# 03_POWER.net
KiCad netlist of a schematic drawn in Altium Designer
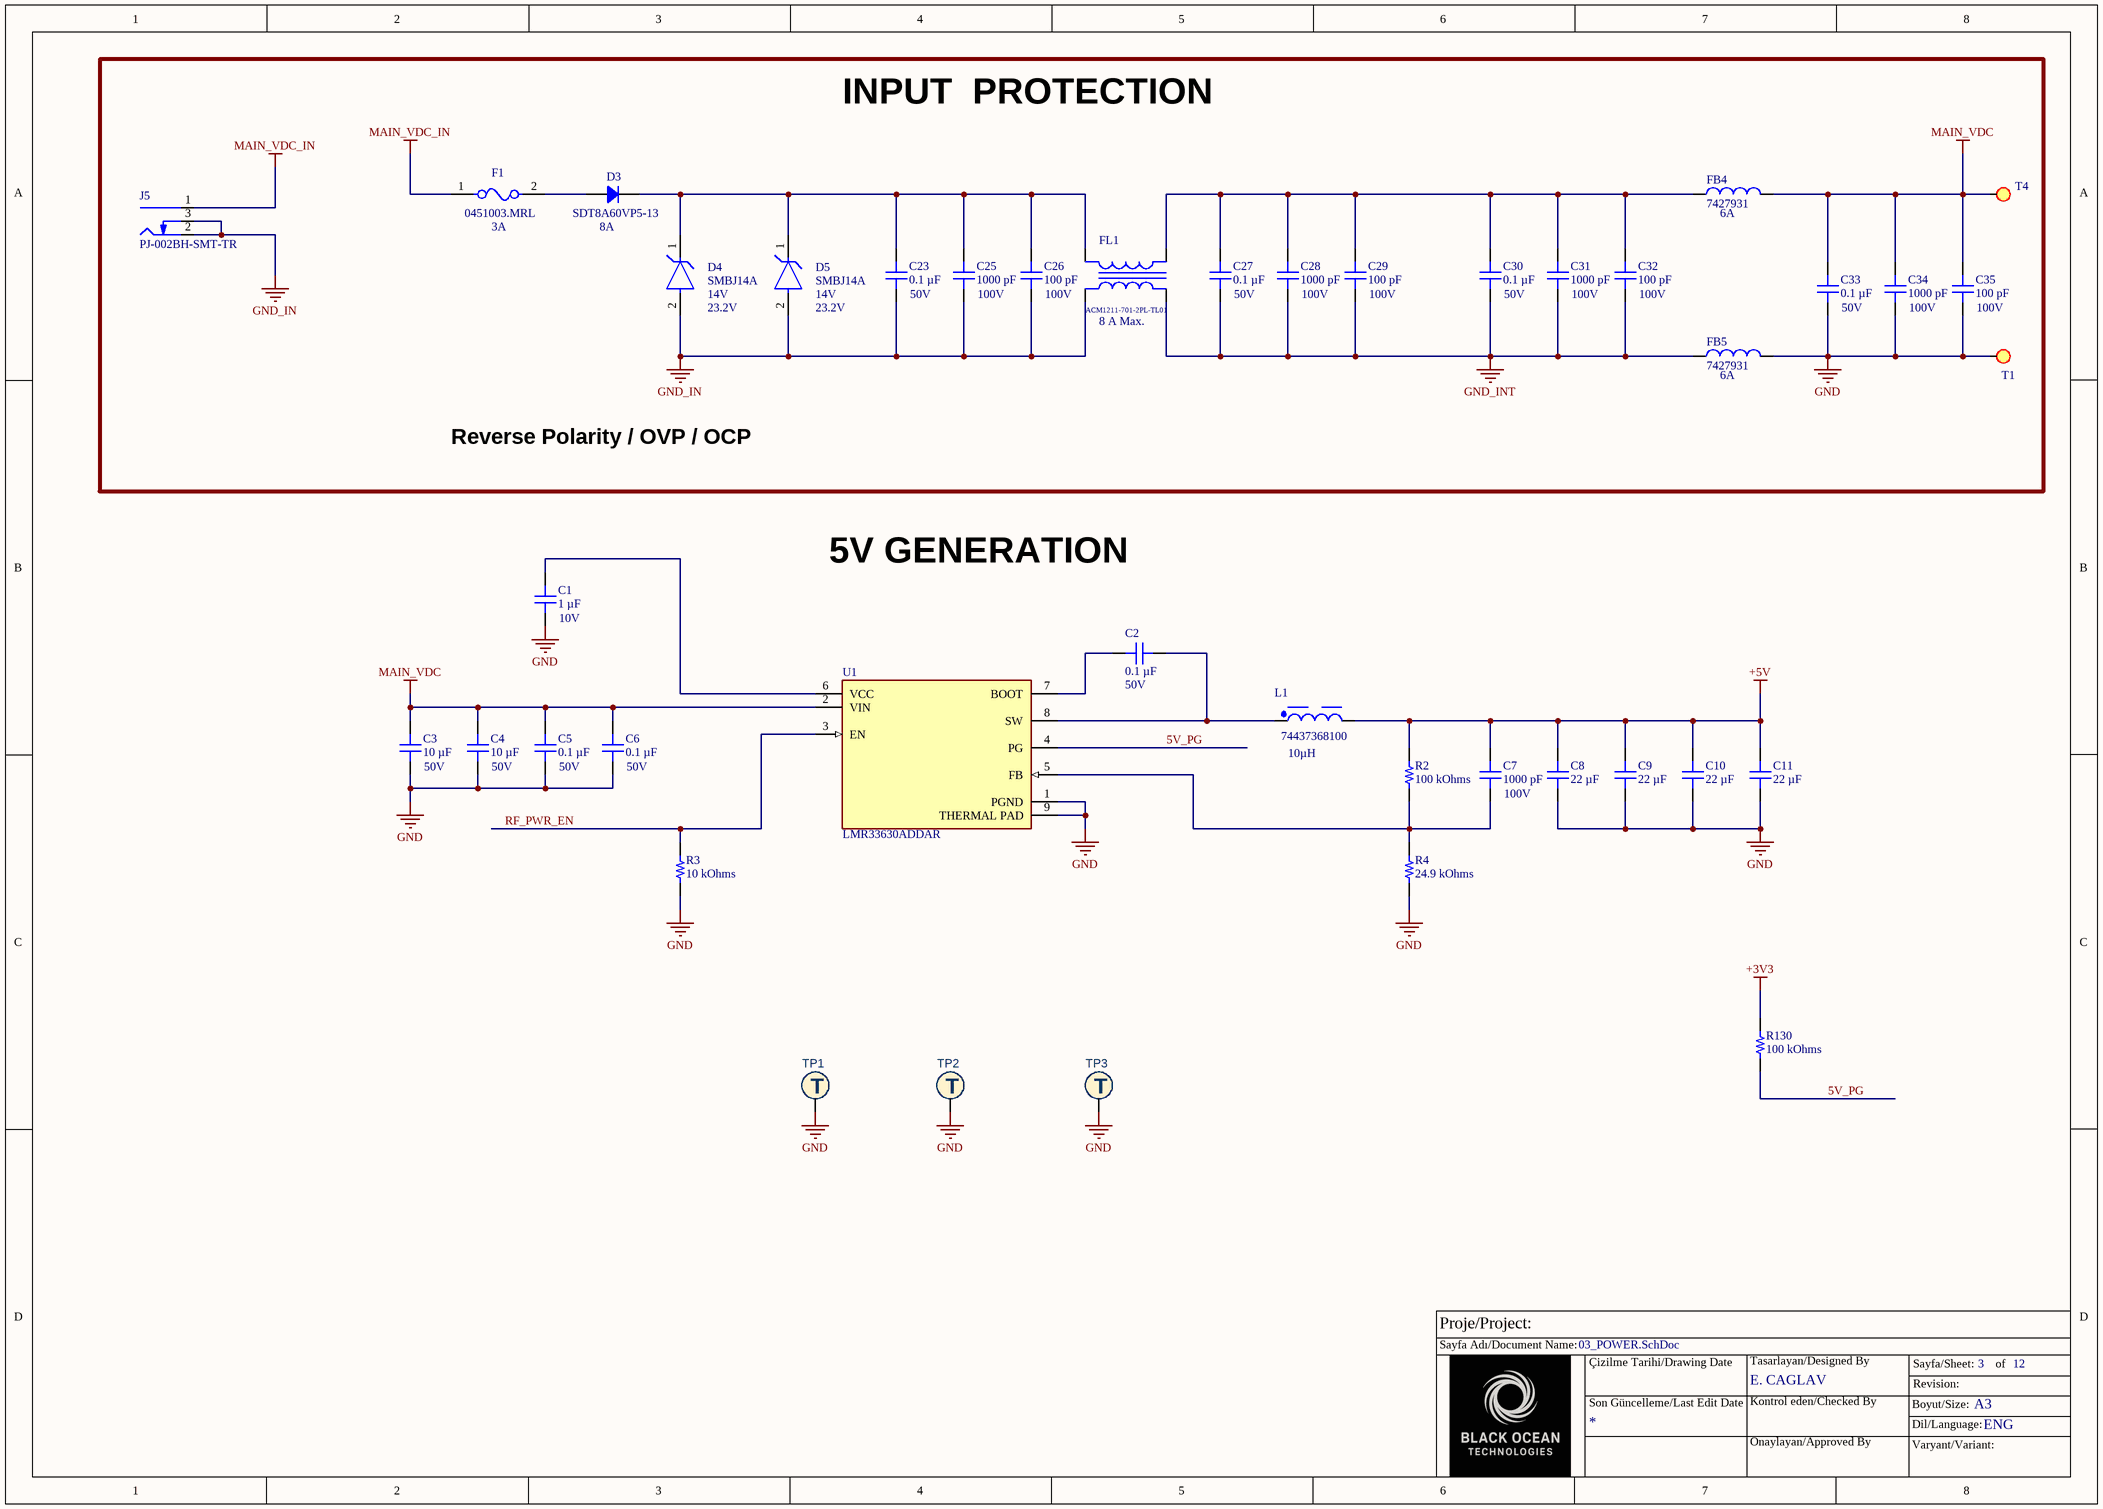
[diagram p0: 03_POWER.SchDoc]

(export (version "E")
  (design (tool "Eeschema 10.0.6"))
  (components
    (comp (ref "C1")
      (value "1 µF")
      (footprint "MURATA GRM155 0402_1005")
      (description "CAP CER 1UF 10V X7S 0402")
      (fields
        (field (name "PART NUMBER") "GRM155C71A105KE11D")
        (field (name "CAPACITANCE") "1 µF")
        (field (name "MANUFACTURER") "Murata Electronics")
        (field (name "VOLTAGE - RATED") "10V")
      )
      (libsource (lib "Celestial Altium Library - altium_library") (part "Capacitor"))
    )
    (comp (ref "C2")
      (value "0.1 µF")
      (footprint "CAP 0402_1005")
      (description "CAP CER 0.1UF 50V X7R 0402")
      (fields
        (field (name "PART NUMBER") "GCM155R71H104KE02J")
        (field (name "CAPACITANCE") "0.1 µF")
        (field (name "MANUFACTURER") "Murata Electronics")
        (field (name "VOLTAGE - RATED") "50V")
      )
      (libsource (lib "Celestial Altium Library - altium_library") (part "Capacitor"))
    )
    (comp (ref "C3")
      (value "10 µF")
      (footprint "CAP 1206_3216 - 0.8MM")
      (description "CAP CER 10UF 50V X7R 1206")
      (fields
        (field (name "PART NUMBER") "CL31B106KBHNNNE")
        (field (name "CAPACITANCE") "10 µF")
        (field (name "MANUFACTURER") "Samsung Electro-Mechanics")
        (field (name "VOLTAGE - RATED") "50V")
      )
      (libsource (lib "Celestial Altium Library - altium_library") (part "Capacitor"))
    )
    (comp (ref "C4")
      (value "10 µF")
      (footprint "CAP 1206_3216 - 0.8MM")
      (description "CAP CER 10UF 50V X7R 1206")
      (fields
        (field (name "PART NUMBER") "CL31B106KBHNNNE")
        (field (name "CAPACITANCE") "10 µF")
        (field (name "MANUFACTURER") "Samsung Electro-Mechanics")
        (field (name "VOLTAGE - RATED") "50V")
      )
      (libsource (lib "Celestial Altium Library - altium_library") (part "Capacitor"))
    )
    (comp (ref "C5")
      (value "0.1 µF")
      (footprint "CAP 0402_1005")
      (description "CAP CER 0.1UF 50V X7R 0402")
      (fields
        (field (name "PART NUMBER") "GCM155R71H104KE02J")
        (field (name "CAPACITANCE") "0.1 µF")
        (field (name "MANUFACTURER") "Murata Electronics")
        (field (name "VOLTAGE - RATED") "50V")
      )
      (libsource (lib "Celestial Altium Library - altium_library") (part "Capacitor"))
    )
    (comp (ref "C6")
      (value "0.1 µF")
      (footprint "CAP 0402_1005")
      (description "CAP CER 0.1UF 50V X7R 0402")
      (fields
        (field (name "PART NUMBER") "GCM155R71H104KE02J")
        (field (name "CAPACITANCE") "0.1 µF")
        (field (name "MANUFACTURER") "Murata Electronics")
        (field (name "VOLTAGE - RATED") "50V")
      )
      (libsource (lib "Celestial Altium Library - altium_library") (part "Capacitor"))
    )
    (comp (ref "C7")
      (value "1000 pF")
      (footprint "CAP 0402_1005")
      (description "CAP CER 1000PF 100V C0G/NP0 0402")
      (fields
        (field (name "PART NUMBER") "C0402H102J1GAC7867")
        (field (name "CAPACITANCE") "1000 pF")
        (field (name "MANUFACTURER") "KEMET")
        (field (name "VOLTAGE - RATED") "100V")
      )
      (libsource (lib "Celestial Altium Library - altium_library") (part "Capacitor"))
    )
    (comp (ref "C8")
      (value "22 µF")
      (footprint "CAP 0805_2012")
      (description "CAP CER 22UF 16V X5R 0805")
      (fields
        (field (name "PART NUMBER") "CL21A226KOQNNNE")
        (field (name "CAPACITANCE") "22 µF")
        (field (name "MANUFACTURER") "Samsung Electro-Mechanics")
      )
      (libsource (lib "Celestial Altium Library - altium_library") (part "Capacitor"))
    )
    (comp (ref "C9")
      (value "22 µF")
      (footprint "CAP 0805_2012")
      (description "CAP CER 22UF 16V X5R 0805")
      (fields
        (field (name "PART NUMBER") "CL21A226KOQNNNE")
        (field (name "CAPACITANCE") "22 µF")
        (field (name "MANUFACTURER") "Samsung Electro-Mechanics")
      )
      (libsource (lib "Celestial Altium Library - altium_library") (part "Capacitor"))
    )
    (comp (ref "C10")
      (value "22 µF")
      (footprint "CAP 0805_2012")
      (description "CAP CER 22UF 16V X5R 0805")
      (fields
        (field (name "PART NUMBER") "CL21A226KOQNNNE")
        (field (name "CAPACITANCE") "22 µF")
        (field (name "MANUFACTURER") "Samsung Electro-Mechanics")
      )
      (libsource (lib "Celestial Altium Library - altium_library") (part "Capacitor"))
    )
    (comp (ref "C11")
      (value "22 µF")
      (footprint "CAP 0805_2012")
      (description "CAP CER 22UF 16V X5R 0805")
      (fields
        (field (name "PART NUMBER") "CL21A226KOQNNNE")
        (field (name "CAPACITANCE") "22 µF")
        (field (name "MANUFACTURER") "Samsung Electro-Mechanics")
      )
      (libsource (lib "Celestial Altium Library - altium_library") (part "Capacitor"))
    )
    (comp (ref "C23")
      (value "0.1 µF")
      (footprint "CAP 0402_1005")
      (description "CAP CER 0.1UF 50V X7R 0402")
      (fields
        (field (name "PART NUMBER") "GCM155R71H104KE02J")
        (field (name "CAPACITANCE") "0.1 µF")
        (field (name "MANUFACTURER") "Murata Electronics")
        (field (name "VOLTAGE - RATED") "50V")
      )
      (libsource (lib "Celestial Altium Library - altium_library") (part "Capacitor"))
    )
    (comp (ref "C25")
      (value "1000 pF")
      (footprint "CAP 0402_1005")
      (description "CAP CER 1000PF 100V C0G/NP0 0402")
      (fields
        (field (name "PART NUMBER") "C0402H102J1GAC7867")
        (field (name "CAPACITANCE") "1000 pF")
        (field (name "MANUFACTURER") "KEMET")
        (field (name "VOLTAGE - RATED") "100V")
      )
      (libsource (lib "Celestial Altium Library - altium_library") (part "Capacitor"))
    )
    (comp (ref "C26")
      (value "100 pF")
      (footprint "CAP 0402_1005")
      (description "CAP CER 100PF 100V C0G/NPO 0402")
      (fields
        (field (name "PART NUMBER") "CC0402JRNPO0BN101")
        (field (name "CAPACITANCE") "100 pF")
        (field (name "MANUFACTURER") "Yageo")
        (field (name "VOLTAGE - RATED") "100V")
      )
      (libsource (lib "Celestial Altium Library - altium_library") (part "Capacitor"))
    )
    (comp (ref "C27")
      (value "0.1 µF")
      (footprint "CAP 0402_1005")
      (description "CAP CER 0.1UF 50V X7R 0402")
      (fields
        (field (name "PART NUMBER") "GCM155R71H104KE02J")
        (field (name "CAPACITANCE") "0.1 µF")
        (field (name "MANUFACTURER") "Murata Electronics")
        (field (name "VOLTAGE - RATED") "50V")
      )
      (libsource (lib "Celestial Altium Library - altium_library") (part "Capacitor"))
    )
    (comp (ref "C28")
      (value "1000 pF")
      (footprint "CAP 0402_1005")
      (description "CAP CER 1000PF 100V C0G/NP0 0402")
      (fields
        (field (name "PART NUMBER") "C0402H102J1GAC7867")
        (field (name "CAPACITANCE") "1000 pF")
        (field (name "MANUFACTURER") "KEMET")
        (field (name "VOLTAGE - RATED") "100V")
      )
      (libsource (lib "Celestial Altium Library - altium_library") (part "Capacitor"))
    )
    (comp (ref "C29")
      (value "100 pF")
      (footprint "CAP 0402_1005")
      (description "CAP CER 100PF 100V C0G/NPO 0402")
      (fields
        (field (name "PART NUMBER") "CC0402JRNPO0BN101")
        (field (name "CAPACITANCE") "100 pF")
        (field (name "MANUFACTURER") "Yageo")
        (field (name "VOLTAGE - RATED") "100V")
      )
      (libsource (lib "Celestial Altium Library - altium_library") (part "Capacitor"))
    )
    (comp (ref "C30")
      (value "0.1 µF")
      (footprint "CAP 0402_1005")
      (description "CAP CER 0.1UF 50V X7R 0402")
      (fields
        (field (name "PART NUMBER") "GCM155R71H104KE02J")
        (field (name "CAPACITANCE") "0.1 µF")
        (field (name "MANUFACTURER") "Murata Electronics")
        (field (name "VOLTAGE - RATED") "50V")
      )
      (libsource (lib "Celestial Altium Library - altium_library") (part "Capacitor"))
    )
    (comp (ref "C31")
      (value "1000 pF")
      (footprint "CAP 0402_1005")
      (description "CAP CER 1000PF 100V C0G/NP0 0402")
      (fields
        (field (name "PART NUMBER") "C0402H102J1GAC7867")
        (field (name "CAPACITANCE") "1000 pF")
        (field (name "MANUFACTURER") "KEMET")
        (field (name "VOLTAGE - RATED") "100V")
      )
      (libsource (lib "Celestial Altium Library - altium_library") (part "Capacitor"))
    )
    (comp (ref "C32")
      (value "100 pF")
      (footprint "CAP 0402_1005")
      (description "CAP CER 100PF 100V C0G/NPO 0402")
      (fields
        (field (name "PART NUMBER") "CC0402JRNPO0BN101")
        (field (name "CAPACITANCE") "100 pF")
        (field (name "MANUFACTURER") "Yageo")
        (field (name "VOLTAGE - RATED") "100V")
      )
      (libsource (lib "Celestial Altium Library - altium_library") (part "Capacitor"))
    )
    (comp (ref "C33")
      (value "0.1 µF")
      (footprint "CAP 0402_1005")
      (description "CAP CER 0.1UF 50V X7R 0402")
      (fields
        (field (name "PART NUMBER") "GCM155R71H104KE02J")
        (field (name "CAPACITANCE") "0.1 µF")
        (field (name "MANUFACTURER") "Murata Electronics")
        (field (name "VOLTAGE - RATED") "50V")
      )
      (libsource (lib "Celestial Altium Library - altium_library") (part "Capacitor"))
    )
    (comp (ref "C34")
      (value "1000 pF")
      (footprint "CAP 0402_1005")
      (description "CAP CER 1000PF 100V C0G/NP0 0402")
      (fields
        (field (name "PART NUMBER") "C0402H102J1GAC7867")
        (field (name "CAPACITANCE") "1000 pF")
        (field (name "MANUFACTURER") "KEMET")
        (field (name "VOLTAGE - RATED") "100V")
      )
      (libsource (lib "Celestial Altium Library - altium_library") (part "Capacitor"))
    )
    (comp (ref "C35")
      (value "100 pF")
      (footprint "CAP 0402_1005")
      (description "CAP CER 100PF 100V C0G/NPO 0402")
      (fields
        (field (name "PART NUMBER") "CC0402JRNPO0BN101")
        (field (name "CAPACITANCE") "100 pF")
        (field (name "MANUFACTURER") "Yageo")
        (field (name "VOLTAGE - RATED") "100V")
      )
      (libsource (lib "Celestial Altium Library - altium_library") (part "Capacitor"))
    )
    (comp (ref "D3")
      (value "SDT8A60VP5-13")
      (footprint "DIODES INC SDT10A45P5")
      (description "DIODE SCHOTTKY 60V 8A PWRDI5 5K")
      (fields
        (field (name "CURRENT - AVERAGE RECTIFIED (IO)") "8A")
        (field (name "MANUFACTURER") "Diodes Incorporated")
      )
      (libsource (lib "Celestial Altium Library - altium_library") (part "DIODE IPC"))
    )
    (comp (ref "D4")
      (value "SMBJ14A")
      (footprint "FP-SMBJ-MFG")
      (description "TVS DIODE 14V 23.2V DO214AA")
      (fields
        (field (name "OCTOPART") "https://octopart.com/smbj14a-taiwan+semiconductor-13998009")
        (field (name "REVERSE STANDOFF VOLTAGE") "14V")
        (field (name "CLAMPING VOLTAGE") "23.2V")
        (field (name "MANUFACTURER") "Taiwan Semiconductor Corporation")
      )
      (libsource (lib "Altium Content Vault") (part "f813f71cba58e380607f5dd3caf9714"))
    )
    (comp (ref "D5")
      (value "SMBJ14A")
      (footprint "FP-SMBJ-MFG")
      (description "TVS DIODE 14V 23.2V DO214AA")
      (fields
        (field (name "OCTOPART") "https://octopart.com/smbj14a-taiwan+semiconductor-13998009")
        (field (name "REVERSE STANDOFF VOLTAGE") "14V")
        (field (name "CLAMPING VOLTAGE") "23.2V")
        (field (name "MANUFACTURER") "Taiwan Semiconductor Corporation")
      )
      (libsource (lib "Altium Content Vault") (part "f813f71cba58e380607f5dd3caf9714"))
    )
    (comp (ref "F1")
      (value "0451003.MRL")
      (footprint "FP-0451-MFG")
      (description "FUSE BRD MNT 3A 125VAC/VDC 2SMD")
      (fields
        (field (name "FUSE CURRENT") "3A")
        (field (name "MANUFACTURER") "Littelfuse Inc")
        (field (name "OCTOPART") "https://octopart.com/0451003.mrl-littelfuse-566380")
      )
      (libsource (lib "Altium Content Vault") (part "5bcf9b9f640e542cf0359d10258e979"))
    )
    (comp (ref "FB4")
      (value "7427931")
      (footprint "WE-PBF_8530_L9.5W3H3.1")
      (fields (field (name "TOLERANCE") "25%") (field (name "CURRENT RATING") "6A"))
      (libsource (lib "Altium Content Vault") (part "Ferrite"))
    )
    (comp (ref "FB5")
      (value "7427931")
      (footprint "WE-PBF_8530_L9.5W3H3.1")
      (fields (field (name "TOLERANCE") "25%") (field (name "CURRENT RATING") "6A"))
      (libsource (lib "Altium Content Vault") (part "Ferrite"))
    )
    (comp (ref "FL1")
      (value "ACM1211-701-2PL-TL01")
      (footprint "TDK-ACM1211-4_V")
      (fields (field (name "MANUFACTURER") "TDK") (field (name "RATED CURRENT") "8 A Max."))
      (libsource (lib "Altium Content Vault") (part "TDK-ACM1211-TL01-4"))
    )
    (comp (ref "J5")
      (value "PJ-002BH-SMT-TR")
      (footprint "CUI PJ-002BH-SMT-TR")
      (description "CONN PWR JACK 2.5X5.5MM SOLDER")
      (fields (field (name "MANUFACTURER") "CUI Devices"))
      (libsource (lib "Celestial Altium Library - altium_library") (part "Barrel Connector"))
    )
    (comp (ref "L1")
      (value "74437368100")
      (footprint "WE-LHMI_1040")
      (description "We-lhmi; 10000NH; Composite Iron Multilayer SMD Induc., 1040 Case; .012GHZ 5.2A")
      (fields (field (name "INDUCTANCE") "10µH") (field (name "TOLERANCE") "20%"))
      (libsource (lib "Altium Content Vault") (part "Inductor - 2"))
    )
    (comp (ref "R2")
      (value "100 kOhms")
      (footprint "RES 0402_1005")
      (description "RES 100K OHM 1% 1/16W 0402")
      (fields (field (name "PART NUMBER") "RC0402FR-13100KL") (field (name "MANUFACTURER") "Yageo"))
      (libsource (lib "Celestial Altium Library - altium_library") (part "Resistor"))
    )
    (comp (ref "R3")
      (value "10 kOhms")
      (footprint "RES 0402_1005")
      (description "RES 10K OHM 1% 1/16W 0402")
      (fields (field (name "PART NUMBER") "RC0402FR-0710KL") (field (name "MANUFACTURER") "Yageo"))
      (libsource (lib "Celestial Altium Library - altium_library") (part "Resistor"))
    )
    (comp (ref "R4")
      (value "24.9 kOhms")
      (footprint "RES 0402_1005")
      (description "RES 24.9K OHM 1% 1/16W 0402")
      (fields (field (name "PART NUMBER") "RC0402FR-0724K9L") (field (name "MANUFACTURER") "Yageo"))
      (libsource (lib "Celestial Altium Library - altium_library") (part "Resistor"))
    )
    (comp (ref "R130")
      (value "100 kOhms")
      (footprint "RES 0402_1005")
      (description "RES SMD 100K OHM 1% 1/16W 0402")
      (fields (field (name "PART NUMBER") "AC0402FR-07100KL") (field (name "MANUFACTURER") "Yageo"))
      (libsource (lib "Celestial Altium Library - altium_library") (part "Resistor"))
    )
    (comp (ref "T1")
      (value "SMD")
      (footprint "TEST_POINT_SMD")
      (libsource (lib "HW_NOMADIQ_2MP_LCD_R1") (part "TP"))
    )
    (comp (ref "T4")
      (value "SMD")
      (footprint "TEST_POINT_SMD")
      (libsource (lib "HW_NOMADIQ_2MP_LCD_R1") (part "TP"))
    )
    (comp (ref "TP1")
      (value "5018")
      (footprint "5018_KEYSTONE")
      (description "MECH PC TEST POINT COMPACT")
      (fields
        (field (name "COMPONENTLINK2URL") "D:\\SAVRONIK_SVN\\Donanım\\trunk\\ALTIUM\\Central Library\\Datasheets\\Mechanical\\5018_Datasheet.pdf")
      )
      (libsource (lib "SMARTCATV") (part "5018"))
    )
    (comp (ref "TP2")
      (value "5018")
      (footprint "5018_KEYSTONE")
      (description "MECH PC TEST POINT COMPACT")
      (fields
        (field (name "COMPONENTLINK2URL") "D:\\SAVRONIK_SVN\\Donanım\\trunk\\ALTIUM\\Central Library\\Datasheets\\Mechanical\\5018_Datasheet.pdf")
      )
      (libsource (lib "SMARTCATV") (part "5018"))
    )
    (comp (ref "TP3")
      (value "5018")
      (footprint "5018_KEYSTONE")
      (description "MECH PC TEST POINT COMPACT")
      (fields
        (field (name "COMPONENTLINK2URL") "D:\\SAVRONIK_SVN\\Donanım\\trunk\\ALTIUM\\Central Library\\Datasheets\\Mechanical\\5018_Datasheet.pdf")
      )
      (libsource (lib "SMARTCATV") (part "5018"))
    )
    (comp (ref "U1")
      (value "LMR33630ADDAR")
      (footprint "FP-DDA0008J-MFG")
      (description "IC REG BUCK ADJUSTABLE 3A 8SOPWR")
      (libsource (lib "Altium Content Vault") (part "6a354f5098e7f60ae670b755afcc2ec"))
    )
  )
  (nets
    (net (code "1") (name "+3V3") (class "Default")
      (node (ref "R130") (pin "2") (pinfunction "2_2") (pintype "passive"))
    )
    (net (code "2") (name "+5V") (class "Default")
      (node (ref "C10") (pin "2") (pinfunction "2_2") (pintype "passive"))
      (node (ref "C11") (pin "2") (pinfunction "2_2") (pintype "passive"))
      (node (ref "C7") (pin "2") (pinfunction "2_2") (pintype "passive"))
      (node (ref "C8") (pin "2") (pinfunction "2_2") (pintype "passive"))
      (node (ref "C9") (pin "2") (pinfunction "2_2") (pintype "passive"))
      (node (ref "L1") (pin "2") (pinfunction "2_2") (pintype "passive"))
      (node (ref "R2") (pin "2") (pinfunction "2_2") (pintype "passive"))
    )
    (net (code "3") (name "/5V_PG") (class "Default")
      (node (ref "R130") (pin "1") (pinfunction "1_1") (pintype "passive"))
      (node (ref "U1") (pin "4") (pinfunction "PG_4") (pintype "open_collector"))
    )
    (net (code "4") (name "/RF_PWR_EN") (class "Default")
      (node (ref "R3") (pin "2") (pinfunction "2_2") (pintype "passive"))
      (node (ref "U1") (pin "3") (pinfunction "EN_3") (pintype "input"))
    )
    (net (code "5") (name "GND") (class "Default")
      (node (ref "C1") (pin "2") (pinfunction "2_2") (pintype "passive"))
      (node (ref "C10") (pin "1") (pinfunction "1_1") (pintype "passive"))
      (node (ref "C11") (pin "1") (pinfunction "1_1") (pintype "passive"))
      (node (ref "C3") (pin "1") (pinfunction "1_1") (pintype "passive"))
      (node (ref "C33") (pin "1") (pinfunction "1_1") (pintype "passive"))
      (node (ref "C34") (pin "1") (pinfunction "1_1") (pintype "passive"))
      (node (ref "C35") (pin "1") (pinfunction "1_1") (pintype "passive"))
      (node (ref "C4") (pin "1") (pinfunction "1_1") (pintype "passive"))
      (node (ref "C5") (pin "1") (pinfunction "1_1") (pintype "passive"))
      (node (ref "C6") (pin "1") (pinfunction "1_1") (pintype "passive"))
      (node (ref "C8") (pin "1") (pinfunction "1_1") (pintype "passive"))
      (node (ref "C9") (pin "1") (pinfunction "1_1") (pintype "passive"))
      (node (ref "FB5") (pin "2") (pinfunction "2_2") (pintype "passive"))
      (node (ref "R3") (pin "1") (pinfunction "1_1") (pintype "passive"))
      (node (ref "R4") (pin "1") (pinfunction "1_1") (pintype "passive"))
      (node (ref "T1") (pin "1") (pinfunction "TP_1") (pintype "passive"))
      (node (ref "TP1") (pin "1") (pintype "passive"))
      (node (ref "TP2") (pin "1") (pintype "passive"))
      (node (ref "TP3") (pin "1") (pintype "passive"))
      (node (ref "U1") (pin "1") (pinfunction "PGND_1") (pintype "power_in"))
      (node (ref "U1") (pin "9") (pinfunction "THERMAL_PAD_9") (pintype "passive"))
    )
    (net (code "6") (name "GND_IN") (class "Default")
      (node (ref "C23") (pin "1") (pinfunction "1_1") (pintype "passive"))
      (node (ref "C25") (pin "1") (pinfunction "1_1") (pintype "passive"))
      (node (ref "C26") (pin "1") (pinfunction "1_1") (pintype "passive"))
      (node (ref "D4") (pin "2") (pinfunction "A_2") (pintype "passive"))
      (node (ref "D5") (pin "2") (pinfunction "A_2") (pintype "passive"))
      (node (ref "FL1") (pin "1") (pinfunction "1_1") (pintype "passive"))
      (node (ref "J5") (pin "2") (pinfunction "Outer_2") (pintype "passive"))
      (node (ref "J5") (pin "3") (pinfunction "SW_3") (pintype "passive"))
    )
    (net (code "7") (name "GND_INT") (class "Default")
      (node (ref "C27") (pin "1") (pinfunction "1_1") (pintype "passive"))
      (node (ref "C28") (pin "1") (pinfunction "1_1") (pintype "passive"))
      (node (ref "C29") (pin "1") (pinfunction "1_1") (pintype "passive"))
      (node (ref "C30") (pin "1") (pinfunction "1_1") (pintype "passive"))
      (node (ref "C31") (pin "1") (pinfunction "1_1") (pintype "passive"))
      (node (ref "C32") (pin "1") (pinfunction "1_1") (pintype "passive"))
      (node (ref "FB5") (pin "1") (pinfunction "1_1") (pintype "passive"))
      (node (ref "FL1") (pin "4") (pinfunction "4_4") (pintype "passive"))
    )
    (net (code "8") (name "MAIN_VDC") (class "Default")
      (node (ref "C3") (pin "2") (pinfunction "2_2") (pintype "passive"))
      (node (ref "C33") (pin "2") (pinfunction "2_2") (pintype "passive"))
      (node (ref "C34") (pin "2") (pinfunction "2_2") (pintype "passive"))
      (node (ref "C35") (pin "2") (pinfunction "2_2") (pintype "passive"))
      (node (ref "C4") (pin "2") (pinfunction "2_2") (pintype "passive"))
      (node (ref "C5") (pin "2") (pinfunction "2_2") (pintype "passive"))
      (node (ref "C6") (pin "2") (pinfunction "2_2") (pintype "passive"))
      (node (ref "FB4") (pin "2") (pinfunction "2_2") (pintype "passive"))
      (node (ref "T4") (pin "1") (pinfunction "TP_1") (pintype "passive"))
      (node (ref "U1") (pin "2") (pinfunction "VIN_2") (pintype "power_in"))
    )
    (net (code "9") (name "MAIN_VDC_IN") (class "Default")
      (node (ref "F1") (pin "1") (pinfunction "1_1") (pintype "passive"))
      (node (ref "J5") (pin "1") (pinfunction "Centre_1") (pintype "passive"))
    )
    (net (code "10") (name "Net-(C27-Pad2)") (class "Default")
      (node (ref "C27") (pin "2") (pinfunction "2_2") (pintype "passive"))
      (node (ref "C28") (pin "2") (pinfunction "2_2") (pintype "passive"))
      (node (ref "C29") (pin "2") (pinfunction "2_2") (pintype "passive"))
      (node (ref "C30") (pin "2") (pinfunction "2_2") (pintype "passive"))
      (node (ref "C31") (pin "2") (pinfunction "2_2") (pintype "passive"))
      (node (ref "C32") (pin "2") (pinfunction "2_2") (pintype "passive"))
      (node (ref "FB4") (pin "1") (pinfunction "1_1") (pintype "passive"))
      (node (ref "FL1") (pin "3") (pinfunction "3_3") (pintype "passive"))
    )
    (net (code "11") (name "Net-(D3-Pad2)") (class "Default")
      (node (ref "D3") (pin "2") (pinfunction "2_2") (pintype "passive"))
      (node (ref "F1") (pin "2") (pinfunction "2_2") (pintype "passive"))
    )
    (net (code "12") (name "Net-(D4-C)") (class "Default")
      (node (ref "C23") (pin "2") (pinfunction "2_2") (pintype "passive"))
      (node (ref "C25") (pin "2") (pinfunction "2_2") (pintype "passive"))
      (node (ref "C26") (pin "2") (pinfunction "2_2") (pintype "passive"))
      (node (ref "D3") (pin "1") (pinfunction "1_1") (pintype "passive"))
      (node (ref "D4") (pin "1") (pinfunction "C_1") (pintype "passive"))
      (node (ref "D5") (pin "1") (pinfunction "C_1") (pintype "passive"))
      (node (ref "FL1") (pin "2") (pinfunction "2_2") (pintype "passive"))
    )
    (net (code "13") (name "Net-(U1-BOOT)") (class "Default")
      (node (ref "C2") (pin "2") (pinfunction "2_2") (pintype "passive"))
      (node (ref "U1") (pin "7") (pinfunction "BOOT_7") (pintype "passive"))
    )
    (net (code "14") (name "Net-(U1-FB)") (class "Default")
      (node (ref "C7") (pin "1") (pinfunction "1_1") (pintype "passive"))
      (node (ref "R2") (pin "1") (pinfunction "1_1") (pintype "passive"))
      (node (ref "R4") (pin "2") (pinfunction "2_2") (pintype "passive"))
      (node (ref "U1") (pin "5") (pinfunction "FB_5") (pintype "input"))
    )
    (net (code "15") (name "Net-(U1-SW)") (class "Default")
      (node (ref "C2") (pin "1") (pinfunction "1_1") (pintype "passive"))
      (node (ref "L1") (pin "1") (pinfunction "1_1") (pintype "passive"))
      (node (ref "U1") (pin "8") (pinfunction "SW_8") (pintype "passive"))
    )
    (net (code "16") (name "Net-(U1-VCC)") (class "Default")
      (node (ref "C1") (pin "1") (pinfunction "1_1") (pintype "passive"))
      (node (ref "U1") (pin "6") (pinfunction "VCC_6") (pintype "power_in"))
    )
  )
)
